# BandpassedGainAmp.net
KiCad netlist of a schematic drawn in EAGLE
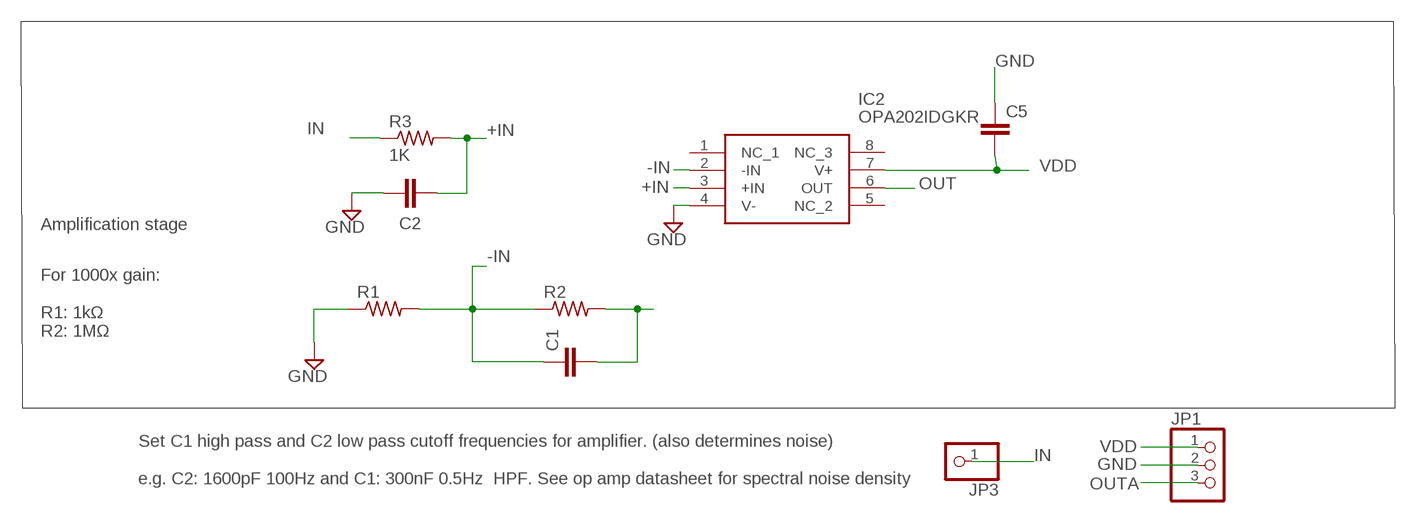
[diagram p0: schematic, sheet 1]

(export (version "E")
  (design (tool "Eeschema 10.0.6"))
  (components
    (comp (ref "C1")
      (value "C-EUC0402")
      (footprint "eagle-import:C0402")
      (libsource (lib "eagle-import") (part "C-EUC0402"))
    )
    (comp (ref "C2")
      (value "C-EUC0402")
      (footprint "eagle-import:C0402")
      (libsource (lib "eagle-import") (part "C-EUC0402"))
    )
    (comp (ref "C5")
      (value "C2.5/2")
      (footprint "eagle-import:C2.5-2")
      (libsource (lib "eagle-import") (part "C2.5/2"))
    )
    (comp (ref "IC2")
      (value "OPA202IDGKR")
      (footprint "eagle-import:SOP65P490X110-8N")
      (fields (field (name "MOUSER_PART_NUMBER") "595-OPA202IDGKR"))
      (libsource (lib "eagle-import") (part "OPA202IDGKR"))
    )
    (comp (ref "JP1")
      (value "PINHD-1X3")
      (footprint "eagle-import:1X03")
      (libsource (lib "eagle-import") (part "PINHD-1X3"))
    )
    (comp (ref "JP3")
      (value "PINHD-1X1")
      (footprint "eagle-import:1X01")
      (libsource (lib "eagle-import") (part "PINHD-1X1"))
    )
    (comp (ref "R1")
      (value "R-US_0204/5")
      (footprint "eagle-import:0204_5")
      (libsource (lib "eagle-import") (part "R-US_0204/5"))
    )
    (comp (ref "R2")
      (value "R-US_0204/5")
      (footprint "eagle-import:0204_5")
      (libsource (lib "eagle-import") (part "R-US_0204/5"))
    )
    (comp (ref "R3")
      (value "1K")
      (footprint "eagle-import:0204_5")
      (libsource (lib "eagle-import") (part "R-US_0204/5"))
    )
  )
  (nets
    (net (code "1") (name "/+IN") (class "Default")
      (node (ref "C2") (pin "2") (pinfunction "2_2") (pintype "passive"))
      (node (ref "IC2") (pin "3") (pinfunction "+IN_3") (pintype "bidirectional"))
      (node (ref "R3") (pin "2") (pinfunction "2_2") (pintype "passive"))
    )
    (net (code "2") (name "/-IN") (class "Default")
      (node (ref "C1") (pin "1") (pinfunction "1_1") (pintype "passive"))
      (node (ref "IC2") (pin "2") (pinfunction "-IN_2") (pintype "bidirectional"))
      (node (ref "R1") (pin "2") (pinfunction "2_2") (pintype "passive"))
      (node (ref "R2") (pin "1") (pinfunction "1_1") (pintype "passive"))
    )
    (net (code "3") (name "/IN") (class "Default")
      (node (ref "JP3") (pin "1") (pinfunction "1_1") (pintype "passive"))
      (node (ref "R3") (pin "1") (pinfunction "1_1") (pintype "passive"))
    )
    (net (code "4") (name "/OUT") (class "Default")
      (node (ref "IC2") (pin "6") (pinfunction "OUT_6") (pintype "bidirectional"))
    )
    (net (code "5") (name "/OUTA") (class "Default")
      (node (ref "JP1") (pin "3") (pinfunction "3_3") (pintype "passive"))
    )
    (net (code "6") (name "/VDD") (class "Default")
      (node (ref "C5") (pin "2") (pinfunction "2_2") (pintype "passive"))
      (node (ref "IC2") (pin "7") (pinfunction "V+_7") (pintype "bidirectional"))
      (node (ref "JP1") (pin "1") (pinfunction "1_1") (pintype "passive"))
    )
    (net (code "7") (name "GND") (class "Default")
      (node (ref "C2") (pin "1") (pinfunction "1_1") (pintype "passive"))
      (node (ref "C5") (pin "1") (pinfunction "1_1") (pintype "passive"))
      (node (ref "IC2") (pin "4") (pinfunction "V-_4") (pintype "bidirectional"))
      (node (ref "JP1") (pin "2") (pinfunction "2_2") (pintype "passive"))
      (node (ref "R1") (pin "1") (pinfunction "1_1") (pintype "passive"))
    )
    (net (code "8") (name "Net-(C1-Pad2)") (class "Default")
      (node (ref "C1") (pin "2") (pinfunction "2_2") (pintype "passive"))
      (node (ref "R2") (pin "2") (pinfunction "2_2") (pintype "passive"))
    )
    (net (code "9") (name "unconnected-(IC2-NC_1-Pad1)") (class "Default")
      (node (ref "IC2") (pin "1") (pinfunction "NC_1_1") (pintype "bidirectional"))
    )
    (net (code "10") (name "unconnected-(IC2-NC_2-Pad5)") (class "Default")
      (node (ref "IC2") (pin "5") (pinfunction "NC_2_5") (pintype "bidirectional"))
    )
    (net (code "11") (name "unconnected-(IC2-NC_3-Pad8)") (class "Default")
      (node (ref "IC2") (pin "8") (pinfunction "NC_3_8") (pintype "bidirectional"))
    )
  )
)
